# TouchProof_Breakout.net
KiCad netlist of a schematic drawn in EAGLE
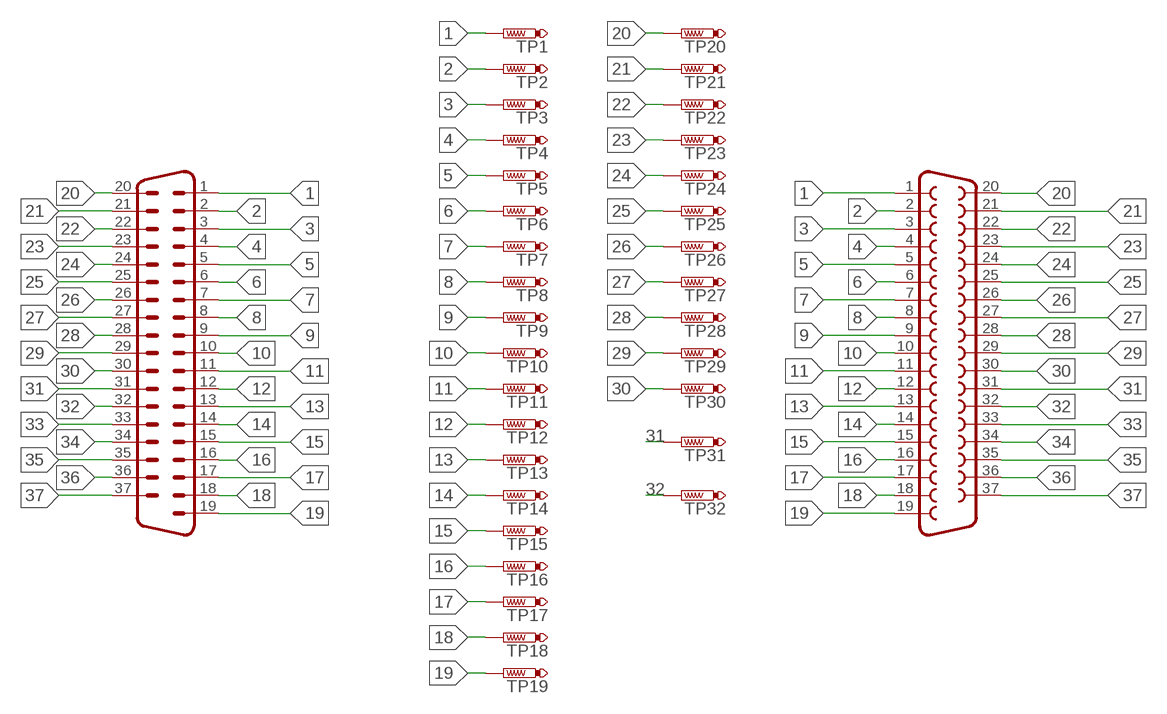
[diagram p0: schematic, sheet 1]

(export (version "E")
  (design (tool "Eeschema 10.0.6"))
  (components
    (comp (ref "TP1")
      (value "TOUCHPROOF")
      (footprint "eagle-import:TOUCHPROOF_PIN")
      (libsource (lib "eagle-import") (part "TOUCHPROOF"))
    )
    (comp (ref "TP2")
      (value "TOUCHPROOF")
      (footprint "eagle-import:TOUCHPROOF_PIN")
      (libsource (lib "eagle-import") (part "TOUCHPROOF"))
    )
    (comp (ref "TP3")
      (value "TOUCHPROOF")
      (footprint "eagle-import:TOUCHPROOF_PIN")
      (libsource (lib "eagle-import") (part "TOUCHPROOF"))
    )
    (comp (ref "TP4")
      (value "TOUCHPROOF")
      (footprint "eagle-import:TOUCHPROOF_PIN")
      (libsource (lib "eagle-import") (part "TOUCHPROOF"))
    )
    (comp (ref "TP5")
      (value "TOUCHPROOF")
      (footprint "eagle-import:TOUCHPROOF_PIN")
      (libsource (lib "eagle-import") (part "TOUCHPROOF"))
    )
    (comp (ref "TP6")
      (value "TOUCHPROOF")
      (footprint "eagle-import:TOUCHPROOF_PIN")
      (libsource (lib "eagle-import") (part "TOUCHPROOF"))
    )
    (comp (ref "TP7")
      (value "TOUCHPROOF")
      (footprint "eagle-import:TOUCHPROOF_PIN")
      (libsource (lib "eagle-import") (part "TOUCHPROOF"))
    )
    (comp (ref "TP8")
      (value "TOUCHPROOF")
      (footprint "eagle-import:TOUCHPROOF_PIN")
      (libsource (lib "eagle-import") (part "TOUCHPROOF"))
    )
    (comp (ref "TP9")
      (value "TOUCHPROOF")
      (footprint "eagle-import:TOUCHPROOF_PIN")
      (libsource (lib "eagle-import") (part "TOUCHPROOF"))
    )
    (comp (ref "TP10")
      (value "TOUCHPROOF")
      (footprint "eagle-import:TOUCHPROOF_PIN")
      (libsource (lib "eagle-import") (part "TOUCHPROOF"))
    )
    (comp (ref "TP11")
      (value "TOUCHPROOF")
      (footprint "eagle-import:TOUCHPROOF_PIN")
      (libsource (lib "eagle-import") (part "TOUCHPROOF"))
    )
    (comp (ref "TP12")
      (value "TOUCHPROOF")
      (footprint "eagle-import:TOUCHPROOF_PIN")
      (libsource (lib "eagle-import") (part "TOUCHPROOF"))
    )
    (comp (ref "TP13")
      (value "TOUCHPROOF")
      (footprint "eagle-import:TOUCHPROOF_PIN")
      (libsource (lib "eagle-import") (part "TOUCHPROOF"))
    )
    (comp (ref "TP14")
      (value "TOUCHPROOF")
      (footprint "eagle-import:TOUCHPROOF_PIN")
      (libsource (lib "eagle-import") (part "TOUCHPROOF"))
    )
    (comp (ref "TP15")
      (value "TOUCHPROOF")
      (footprint "eagle-import:TOUCHPROOF_PIN")
      (libsource (lib "eagle-import") (part "TOUCHPROOF"))
    )
    (comp (ref "TP16")
      (value "TOUCHPROOF")
      (footprint "eagle-import:TOUCHPROOF_PIN")
      (libsource (lib "eagle-import") (part "TOUCHPROOF"))
    )
    (comp (ref "TP17")
      (value "TOUCHPROOF")
      (footprint "eagle-import:TOUCHPROOF_PIN")
      (libsource (lib "eagle-import") (part "TOUCHPROOF"))
    )
    (comp (ref "TP18")
      (value "TOUCHPROOF")
      (footprint "eagle-import:TOUCHPROOF_PIN")
      (libsource (lib "eagle-import") (part "TOUCHPROOF"))
    )
    (comp (ref "TP19")
      (value "TOUCHPROOF")
      (footprint "eagle-import:TOUCHPROOF_PIN")
      (libsource (lib "eagle-import") (part "TOUCHPROOF"))
    )
    (comp (ref "TP20")
      (value "TOUCHPROOF")
      (footprint "eagle-import:TOUCHPROOF_PIN")
      (libsource (lib "eagle-import") (part "TOUCHPROOF"))
    )
    (comp (ref "TP21")
      (value "TOUCHPROOF")
      (footprint "eagle-import:TOUCHPROOF_PIN")
      (libsource (lib "eagle-import") (part "TOUCHPROOF"))
    )
    (comp (ref "TP22")
      (value "TOUCHPROOF")
      (footprint "eagle-import:TOUCHPROOF_PIN")
      (libsource (lib "eagle-import") (part "TOUCHPROOF"))
    )
    (comp (ref "TP23")
      (value "TOUCHPROOF")
      (footprint "eagle-import:TOUCHPROOF_PIN")
      (libsource (lib "eagle-import") (part "TOUCHPROOF"))
    )
    (comp (ref "TP24")
      (value "TOUCHPROOF")
      (footprint "eagle-import:TOUCHPROOF_PIN")
      (libsource (lib "eagle-import") (part "TOUCHPROOF"))
    )
    (comp (ref "TP25")
      (value "TOUCHPROOF")
      (footprint "eagle-import:TOUCHPROOF_PIN")
      (libsource (lib "eagle-import") (part "TOUCHPROOF"))
    )
    (comp (ref "TP26")
      (value "TOUCHPROOF")
      (footprint "eagle-import:TOUCHPROOF_PIN")
      (libsource (lib "eagle-import") (part "TOUCHPROOF"))
    )
    (comp (ref "TP27")
      (value "TOUCHPROOF")
      (footprint "eagle-import:TOUCHPROOF_PIN")
      (libsource (lib "eagle-import") (part "TOUCHPROOF"))
    )
    (comp (ref "TP28")
      (value "TOUCHPROOF")
      (footprint "eagle-import:TOUCHPROOF_PIN")
      (libsource (lib "eagle-import") (part "TOUCHPROOF"))
    )
    (comp (ref "TP29")
      (value "TOUCHPROOF")
      (footprint "eagle-import:TOUCHPROOF_PIN")
      (libsource (lib "eagle-import") (part "TOUCHPROOF"))
    )
    (comp (ref "TP30")
      (value "TOUCHPROOF")
      (footprint "eagle-import:TOUCHPROOF_PIN")
      (libsource (lib "eagle-import") (part "TOUCHPROOF"))
    )
    (comp (ref "TP31")
      (value "TOUCHPROOF")
      (footprint "eagle-import:TOUCHPROOF_PIN")
      (libsource (lib "eagle-import") (part "TOUCHPROOF"))
    )
    (comp (ref "TP32")
      (value "TOUCHPROOF")
      (footprint "eagle-import:TOUCHPROOF_PIN")
      (libsource (lib "eagle-import") (part "TOUCHPROOF"))
    )
    (comp (ref "X40")
      (value "M37HP")
      (footprint "eagle-import:M37HP")
      (libsource (lib "eagle-import") (part "M37HP"))
    )
    (comp (ref "X41")
      (value "F37HP")
      (footprint "eagle-import:F37HP")
      (libsource (lib "eagle-import") (part "F37HP"))
    )
  )
  (nets
    (net (code "1") (name "1") (class "Default")
      (node (ref "TP1") (pin "TP") (pinfunction "TP_TP") (pintype "input"))
      (node (ref "X40") (pin "1") (pinfunction "1_1") (pintype "passive"))
      (node (ref "X41") (pin "1") (pinfunction "1_1") (pintype "passive"))
    )
    (net (code "2") (name "2") (class "Default")
      (node (ref "TP2") (pin "TP") (pinfunction "TP_TP") (pintype "input"))
      (node (ref "X40") (pin "2") (pinfunction "2_2") (pintype "passive"))
      (node (ref "X41") (pin "2") (pinfunction "2_2") (pintype "passive"))
    )
    (net (code "3") (name "3") (class "Default")
      (node (ref "TP3") (pin "TP") (pinfunction "TP_TP") (pintype "input"))
      (node (ref "X40") (pin "3") (pinfunction "3_3") (pintype "passive"))
      (node (ref "X41") (pin "3") (pinfunction "3_3") (pintype "passive"))
    )
    (net (code "4") (name "4") (class "Default")
      (node (ref "TP4") (pin "TP") (pinfunction "TP_TP") (pintype "input"))
      (node (ref "X40") (pin "4") (pinfunction "4_4") (pintype "passive"))
      (node (ref "X41") (pin "4") (pinfunction "4_4") (pintype "passive"))
    )
    (net (code "5") (name "5") (class "Default")
      (node (ref "TP5") (pin "TP") (pinfunction "TP_TP") (pintype "input"))
      (node (ref "X40") (pin "5") (pinfunction "5_5") (pintype "passive"))
      (node (ref "X41") (pin "5") (pinfunction "5_5") (pintype "passive"))
    )
    (net (code "6") (name "6") (class "Default")
      (node (ref "TP6") (pin "TP") (pinfunction "TP_TP") (pintype "input"))
      (node (ref "X40") (pin "6") (pinfunction "6_6") (pintype "passive"))
      (node (ref "X41") (pin "6") (pinfunction "6_6") (pintype "passive"))
    )
    (net (code "7") (name "7") (class "Default")
      (node (ref "TP7") (pin "TP") (pinfunction "TP_TP") (pintype "input"))
      (node (ref "X40") (pin "7") (pinfunction "7_7") (pintype "passive"))
      (node (ref "X41") (pin "7") (pinfunction "7_7") (pintype "passive"))
    )
    (net (code "8") (name "8") (class "Default")
      (node (ref "TP8") (pin "TP") (pinfunction "TP_TP") (pintype "input"))
      (node (ref "X40") (pin "8") (pinfunction "8_8") (pintype "passive"))
      (node (ref "X41") (pin "8") (pinfunction "8_8") (pintype "passive"))
    )
    (net (code "9") (name "9") (class "Default")
      (node (ref "TP9") (pin "TP") (pinfunction "TP_TP") (pintype "input"))
      (node (ref "X40") (pin "9") (pinfunction "9_9") (pintype "passive"))
      (node (ref "X41") (pin "9") (pinfunction "9_9") (pintype "passive"))
    )
    (net (code "10") (name "10") (class "Default")
      (node (ref "TP10") (pin "TP") (pinfunction "TP_TP") (pintype "input"))
      (node (ref "X40") (pin "10") (pinfunction "10_10") (pintype "passive"))
      (node (ref "X41") (pin "10") (pinfunction "10_10") (pintype "passive"))
    )
    (net (code "11") (name "11") (class "Default")
      (node (ref "TP11") (pin "TP") (pinfunction "TP_TP") (pintype "input"))
      (node (ref "X40") (pin "11") (pinfunction "11_11") (pintype "passive"))
      (node (ref "X41") (pin "11") (pinfunction "11_11") (pintype "passive"))
    )
    (net (code "12") (name "12") (class "Default")
      (node (ref "TP12") (pin "TP") (pinfunction "TP_TP") (pintype "input"))
      (node (ref "X40") (pin "12") (pinfunction "12_12") (pintype "passive"))
      (node (ref "X41") (pin "12") (pinfunction "12_12") (pintype "passive"))
    )
    (net (code "13") (name "13") (class "Default")
      (node (ref "TP13") (pin "TP") (pinfunction "TP_TP") (pintype "input"))
      (node (ref "X40") (pin "13") (pinfunction "13_13") (pintype "passive"))
      (node (ref "X41") (pin "13") (pinfunction "13_13") (pintype "passive"))
    )
    (net (code "14") (name "14") (class "Default")
      (node (ref "TP14") (pin "TP") (pinfunction "TP_TP") (pintype "input"))
      (node (ref "X40") (pin "14") (pinfunction "14_14") (pintype "passive"))
      (node (ref "X41") (pin "14") (pinfunction "14_14") (pintype "passive"))
    )
    (net (code "15") (name "15") (class "Default")
      (node (ref "TP15") (pin "TP") (pinfunction "TP_TP") (pintype "input"))
      (node (ref "X40") (pin "15") (pinfunction "15_15") (pintype "passive"))
      (node (ref "X41") (pin "15") (pinfunction "15_15") (pintype "passive"))
    )
    (net (code "16") (name "16") (class "Default")
      (node (ref "TP16") (pin "TP") (pinfunction "TP_TP") (pintype "input"))
      (node (ref "X40") (pin "16") (pinfunction "16_16") (pintype "passive"))
      (node (ref "X41") (pin "16") (pinfunction "16_16") (pintype "passive"))
    )
    (net (code "17") (name "17") (class "Default")
      (node (ref "TP17") (pin "TP") (pinfunction "TP_TP") (pintype "input"))
      (node (ref "X40") (pin "17") (pinfunction "17_17") (pintype "passive"))
      (node (ref "X41") (pin "17") (pinfunction "17_17") (pintype "passive"))
    )
    (net (code "18") (name "18") (class "Default")
      (node (ref "TP18") (pin "TP") (pinfunction "TP_TP") (pintype "input"))
      (node (ref "X40") (pin "18") (pinfunction "18_18") (pintype "passive"))
      (node (ref "X41") (pin "18") (pinfunction "18_18") (pintype "passive"))
    )
    (net (code "19") (name "19") (class "Default")
      (node (ref "TP19") (pin "TP") (pinfunction "TP_TP") (pintype "input"))
      (node (ref "X40") (pin "19") (pinfunction "19_19") (pintype "passive"))
      (node (ref "X41") (pin "19") (pinfunction "19_19") (pintype "passive"))
    )
    (net (code "20") (name "20") (class "Default")
      (node (ref "TP20") (pin "TP") (pinfunction "TP_TP") (pintype "input"))
      (node (ref "X40") (pin "20") (pinfunction "20_20") (pintype "passive"))
      (node (ref "X41") (pin "20") (pinfunction "20_20") (pintype "passive"))
    )
    (net (code "21") (name "21") (class "Default")
      (node (ref "TP21") (pin "TP") (pinfunction "TP_TP") (pintype "input"))
      (node (ref "X40") (pin "21") (pinfunction "21_21") (pintype "passive"))
      (node (ref "X41") (pin "21") (pinfunction "21_21") (pintype "passive"))
    )
    (net (code "22") (name "22") (class "Default")
      (node (ref "TP22") (pin "TP") (pinfunction "TP_TP") (pintype "input"))
      (node (ref "X40") (pin "22") (pinfunction "22_22") (pintype "passive"))
      (node (ref "X41") (pin "22") (pinfunction "22_22") (pintype "passive"))
    )
    (net (code "23") (name "23") (class "Default")
      (node (ref "TP23") (pin "TP") (pinfunction "TP_TP") (pintype "input"))
      (node (ref "X40") (pin "23") (pinfunction "23_23") (pintype "passive"))
      (node (ref "X41") (pin "23") (pinfunction "23_23") (pintype "passive"))
    )
    (net (code "24") (name "24") (class "Default")
      (node (ref "TP24") (pin "TP") (pinfunction "TP_TP") (pintype "input"))
      (node (ref "X40") (pin "24") (pinfunction "24_24") (pintype "passive"))
      (node (ref "X41") (pin "24") (pinfunction "24_24") (pintype "passive"))
    )
    (net (code "25") (name "25") (class "Default")
      (node (ref "TP25") (pin "TP") (pinfunction "TP_TP") (pintype "input"))
      (node (ref "X40") (pin "25") (pinfunction "25_25") (pintype "passive"))
      (node (ref "X41") (pin "25") (pinfunction "25_25") (pintype "passive"))
    )
    (net (code "26") (name "26") (class "Default")
      (node (ref "TP26") (pin "TP") (pinfunction "TP_TP") (pintype "input"))
      (node (ref "X40") (pin "26") (pinfunction "26_26") (pintype "passive"))
      (node (ref "X41") (pin "26") (pinfunction "26_26") (pintype "passive"))
    )
    (net (code "27") (name "27") (class "Default")
      (node (ref "TP27") (pin "TP") (pinfunction "TP_TP") (pintype "input"))
      (node (ref "X40") (pin "27") (pinfunction "27_27") (pintype "passive"))
      (node (ref "X41") (pin "27") (pinfunction "27_27") (pintype "passive"))
    )
    (net (code "28") (name "28") (class "Default")
      (node (ref "TP28") (pin "TP") (pinfunction "TP_TP") (pintype "input"))
      (node (ref "X40") (pin "28") (pinfunction "28_28") (pintype "passive"))
      (node (ref "X41") (pin "28") (pinfunction "28_28") (pintype "passive"))
    )
    (net (code "29") (name "29") (class "Default")
      (node (ref "TP29") (pin "TP") (pinfunction "TP_TP") (pintype "input"))
      (node (ref "X40") (pin "29") (pinfunction "29_29") (pintype "passive"))
      (node (ref "X41") (pin "29") (pinfunction "29_29") (pintype "passive"))
    )
    (net (code "30") (name "30") (class "Default")
      (node (ref "TP30") (pin "TP") (pinfunction "TP_TP") (pintype "input"))
      (node (ref "X40") (pin "30") (pinfunction "30_30") (pintype "passive"))
      (node (ref "X41") (pin "30") (pinfunction "30_30") (pintype "passive"))
    )
    (net (code "31") (name "31") (class "Default")
      (node (ref "TP31") (pin "TP") (pinfunction "TP_TP") (pintype "input"))
      (node (ref "X40") (pin "31") (pinfunction "31_31") (pintype "passive"))
      (node (ref "X41") (pin "31") (pinfunction "31_31") (pintype "passive"))
    )
    (net (code "32") (name "32") (class "Default")
      (node (ref "TP32") (pin "TP") (pinfunction "TP_TP") (pintype "input"))
      (node (ref "X40") (pin "32") (pinfunction "32_32") (pintype "passive"))
      (node (ref "X41") (pin "32") (pinfunction "32_32") (pintype "passive"))
    )
    (net (code "33") (name "33") (class "Default")
      (node (ref "X40") (pin "33") (pinfunction "33_33") (pintype "passive"))
      (node (ref "X41") (pin "33") (pinfunction "33_33") (pintype "passive"))
    )
    (net (code "34") (name "34") (class "Default")
      (node (ref "X40") (pin "34") (pinfunction "34_34") (pintype "passive"))
      (node (ref "X41") (pin "34") (pinfunction "34_34") (pintype "passive"))
    )
    (net (code "35") (name "35") (class "Default")
      (node (ref "X40") (pin "35") (pinfunction "35_35") (pintype "passive"))
      (node (ref "X41") (pin "35") (pinfunction "35_35") (pintype "passive"))
    )
    (net (code "36") (name "36") (class "Default")
      (node (ref "X40") (pin "36") (pinfunction "36_36") (pintype "passive"))
      (node (ref "X41") (pin "36") (pinfunction "36_36") (pintype "passive"))
    )
    (net (code "37") (name "37") (class "Default")
      (node (ref "X40") (pin "37") (pinfunction "37_37") (pintype "passive"))
      (node (ref "X41") (pin "37") (pinfunction "37_37") (pintype "passive"))
    )
  )
)
